# DEC8L-buscon.net
KiCad netlist of a schematic drawn in EAGLE
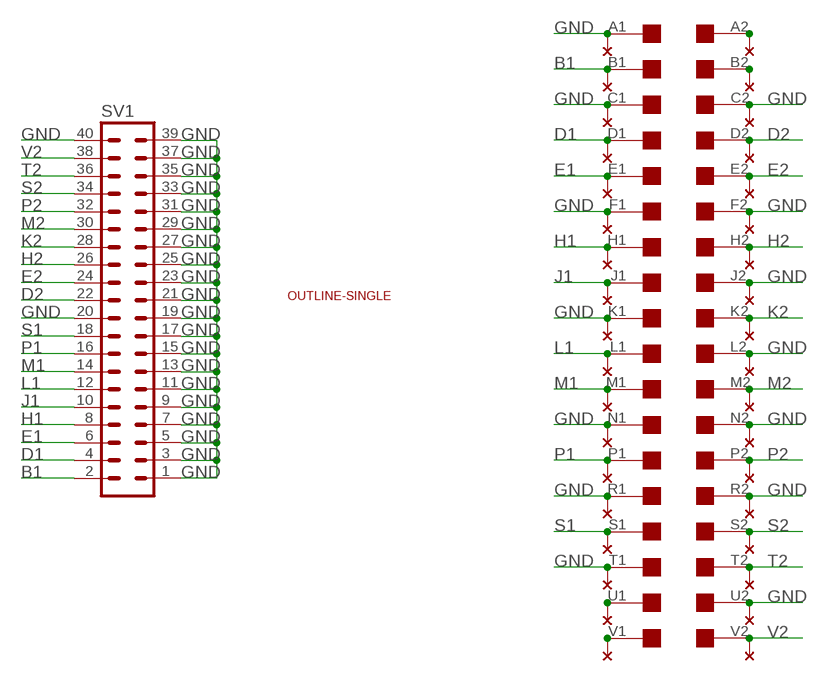
[diagram p0: schematic, sheet 1]

(export (version "E")
  (design (tool "Eeschema 10.0.6"))
  (components
    (comp (ref "EDGE1")
      (value "EDGE-2CONNECTOR")
      (footprint "eagle-import:EDGE-CON2")
      (libsource (lib "eagle-import") (part "EDGE-2CONNECTOR"))
    )
    (comp (ref "SV1")
      (value "MA20-2")
      (footprint "eagle-import:MA20-2")
      (libsource (lib "eagle-import") (part "MA20-2"))
    )
    (comp (ref "U$4")
      (value "OUTLINE-SINGLE")
      (footprint "eagle-import:SINGLE")
      (libsource (lib "eagle-import") (part "OUTLINE-SINGLE"))
    )
    (comp (ref "U$5")
      (value "THRU-HOLE2")
      (footprint "eagle-import:THRU-HOLEB")
      (libsource (lib "eagle-import") (part "THRU-HOLE2"))
    )
  )
  (nets
    (net (code "1") (name "/B1") (class "Default")
      (node (ref "EDGE1") (pin "B1") (pinfunction "1_B1") (pintype "bidirectional"))
      (node (ref "SV1") (pin "2") (pinfunction "2_2") (pintype "passive"))
      (node (ref "U$5") (pin "B1") (pinfunction "P$1_B1") (pintype "passive"))
    )
    (net (code "2") (name "/D1") (class "Default")
      (node (ref "EDGE1") (pin "D1") (pinfunction "1_D1") (pintype "bidirectional"))
      (node (ref "SV1") (pin "4") (pinfunction "4_4") (pintype "passive"))
      (node (ref "U$5") (pin "D1") (pinfunction "P$1_D1") (pintype "passive"))
    )
    (net (code "3") (name "/D2") (class "Default")
      (node (ref "EDGE1") (pin "D2") (pinfunction "1_D2") (pintype "bidirectional"))
      (node (ref "SV1") (pin "22") (pinfunction "22_22") (pintype "passive"))
      (node (ref "U$5") (pin "D2") (pinfunction "P$1_D2") (pintype "passive"))
    )
    (net (code "4") (name "/E1") (class "Default")
      (node (ref "EDGE1") (pin "E1") (pinfunction "1_E1") (pintype "bidirectional"))
      (node (ref "SV1") (pin "6") (pinfunction "6_6") (pintype "passive"))
      (node (ref "U$5") (pin "E1") (pinfunction "P$1_E1") (pintype "passive"))
    )
    (net (code "5") (name "/E2") (class "Default")
      (node (ref "EDGE1") (pin "E2") (pinfunction "1_E2") (pintype "bidirectional"))
      (node (ref "SV1") (pin "24") (pinfunction "24_24") (pintype "passive"))
      (node (ref "U$5") (pin "E2") (pinfunction "P$1_E2") (pintype "passive"))
    )
    (net (code "6") (name "/GND") (class "Default")
      (node (ref "EDGE1") (pin "A1") (pinfunction "1_A1") (pintype "bidirectional"))
      (node (ref "EDGE1") (pin "C1") (pinfunction "1_C1") (pintype "bidirectional"))
      (node (ref "EDGE1") (pin "C2") (pinfunction "1_C2") (pintype "bidirectional"))
      (node (ref "EDGE1") (pin "F1") (pinfunction "1_F1") (pintype "bidirectional"))
      (node (ref "EDGE1") (pin "F2") (pinfunction "1_F2") (pintype "bidirectional"))
      (node (ref "EDGE1") (pin "J2") (pinfunction "1_J2") (pintype "bidirectional"))
      (node (ref "EDGE1") (pin "K1") (pinfunction "1_K1") (pintype "bidirectional"))
      (node (ref "EDGE1") (pin "L2") (pinfunction "1_L2") (pintype "bidirectional"))
      (node (ref "EDGE1") (pin "N1") (pinfunction "1_N1") (pintype "bidirectional"))
      (node (ref "EDGE1") (pin "N2") (pinfunction "1_N2") (pintype "bidirectional"))
      (node (ref "EDGE1") (pin "R1") (pinfunction "1_R1") (pintype "bidirectional"))
      (node (ref "EDGE1") (pin "R2") (pinfunction "1_R2") (pintype "bidirectional"))
      (node (ref "EDGE1") (pin "T1") (pinfunction "1_T1") (pintype "bidirectional"))
      (node (ref "EDGE1") (pin "U2") (pinfunction "1_U2") (pintype "bidirectional"))
      (node (ref "SV1") (pin "1") (pinfunction "1_1") (pintype "passive"))
      (node (ref "SV1") (pin "11") (pinfunction "11_11") (pintype "passive"))
      (node (ref "SV1") (pin "13") (pinfunction "13_13") (pintype "passive"))
      (node (ref "SV1") (pin "15") (pinfunction "15_15") (pintype "passive"))
      (node (ref "SV1") (pin "17") (pinfunction "17_17") (pintype "passive"))
      (node (ref "SV1") (pin "19") (pinfunction "19_19") (pintype "passive"))
      (node (ref "SV1") (pin "20") (pinfunction "20_20") (pintype "passive"))
      (node (ref "SV1") (pin "21") (pinfunction "21_21") (pintype "passive"))
      (node (ref "SV1") (pin "23") (pinfunction "23_23") (pintype "passive"))
      (node (ref "SV1") (pin "25") (pinfunction "25_25") (pintype "passive"))
      (node (ref "SV1") (pin "27") (pinfunction "27_27") (pintype "passive"))
      (node (ref "SV1") (pin "29") (pinfunction "29_29") (pintype "passive"))
      (node (ref "SV1") (pin "3") (pinfunction "3_3") (pintype "passive"))
      (node (ref "SV1") (pin "31") (pinfunction "31_31") (pintype "passive"))
      (node (ref "SV1") (pin "33") (pinfunction "33_33") (pintype "passive"))
      (node (ref "SV1") (pin "35") (pinfunction "35_35") (pintype "passive"))
      (node (ref "SV1") (pin "37") (pinfunction "37_37") (pintype "passive"))
      (node (ref "SV1") (pin "39") (pinfunction "39_39") (pintype "passive"))
      (node (ref "SV1") (pin "40") (pinfunction "40_40") (pintype "passive"))
      (node (ref "SV1") (pin "5") (pinfunction "5_5") (pintype "passive"))
      (node (ref "SV1") (pin "7") (pinfunction "7_7") (pintype "passive"))
      (node (ref "SV1") (pin "9") (pinfunction "9_9") (pintype "passive"))
      (node (ref "U$5") (pin "A1") (pinfunction "P$1_A1") (pintype "passive"))
      (node (ref "U$5") (pin "C1") (pinfunction "P$1_C1") (pintype "passive"))
      (node (ref "U$5") (pin "C2") (pinfunction "P$1_C2") (pintype "passive"))
      (node (ref "U$5") (pin "F1") (pinfunction "P$1_F1") (pintype "passive"))
      (node (ref "U$5") (pin "F2") (pinfunction "P$1_F2") (pintype "passive"))
      (node (ref "U$5") (pin "J2") (pinfunction "P$1_J2") (pintype "passive"))
      (node (ref "U$5") (pin "K1") (pinfunction "P$1_K1") (pintype "passive"))
      (node (ref "U$5") (pin "L2") (pinfunction "P$1_L2") (pintype "passive"))
      (node (ref "U$5") (pin "N1") (pinfunction "P$1_N1") (pintype "passive"))
      (node (ref "U$5") (pin "N2") (pinfunction "P$1_N2") (pintype "passive"))
      (node (ref "U$5") (pin "R1") (pinfunction "P$1_R1") (pintype "passive"))
      (node (ref "U$5") (pin "R2") (pinfunction "P$1_R2") (pintype "passive"))
      (node (ref "U$5") (pin "T1") (pinfunction "P$1_T1") (pintype "passive"))
      (node (ref "U$5") (pin "U2") (pinfunction "P$1_U2") (pintype "passive"))
    )
    (net (code "7") (name "/H1") (class "Default")
      (node (ref "EDGE1") (pin "H1") (pinfunction "1_H1") (pintype "bidirectional"))
      (node (ref "SV1") (pin "8") (pinfunction "8_8") (pintype "passive"))
      (node (ref "U$5") (pin "H1") (pinfunction "P$1_H1") (pintype "passive"))
    )
    (net (code "8") (name "/H2") (class "Default")
      (node (ref "EDGE1") (pin "H2") (pinfunction "1_H2") (pintype "bidirectional"))
      (node (ref "SV1") (pin "26") (pinfunction "26_26") (pintype "passive"))
      (node (ref "U$5") (pin "H2") (pinfunction "P$1_H2") (pintype "passive"))
    )
    (net (code "9") (name "/J1") (class "Default")
      (node (ref "EDGE1") (pin "J1") (pinfunction "1_J1") (pintype "bidirectional"))
      (node (ref "SV1") (pin "10") (pinfunction "10_10") (pintype "passive"))
      (node (ref "U$5") (pin "J1") (pinfunction "P$1_J1") (pintype "passive"))
    )
    (net (code "10") (name "/K2") (class "Default")
      (node (ref "EDGE1") (pin "K2") (pinfunction "1_K2") (pintype "bidirectional"))
      (node (ref "SV1") (pin "28") (pinfunction "28_28") (pintype "passive"))
      (node (ref "U$5") (pin "K2") (pinfunction "P$1_K2") (pintype "passive"))
    )
    (net (code "11") (name "/L1") (class "Default")
      (node (ref "EDGE1") (pin "L1") (pinfunction "1_L1") (pintype "bidirectional"))
      (node (ref "SV1") (pin "12") (pinfunction "12_12") (pintype "passive"))
      (node (ref "U$5") (pin "L1") (pinfunction "P$1_L1") (pintype "passive"))
    )
    (net (code "12") (name "/M1") (class "Default")
      (node (ref "EDGE1") (pin "M1") (pinfunction "1_M1") (pintype "bidirectional"))
      (node (ref "SV1") (pin "14") (pinfunction "14_14") (pintype "passive"))
      (node (ref "U$5") (pin "M1") (pinfunction "P$1_M1") (pintype "passive"))
    )
    (net (code "13") (name "/M2") (class "Default")
      (node (ref "EDGE1") (pin "M2") (pinfunction "1_M2") (pintype "bidirectional"))
      (node (ref "SV1") (pin "30") (pinfunction "30_30") (pintype "passive"))
      (node (ref "U$5") (pin "M2") (pinfunction "P$1_M2") (pintype "passive"))
    )
    (net (code "14") (name "/P1") (class "Default")
      (node (ref "EDGE1") (pin "P1") (pinfunction "1_P1") (pintype "bidirectional"))
      (node (ref "SV1") (pin "16") (pinfunction "16_16") (pintype "passive"))
      (node (ref "U$5") (pin "P1") (pinfunction "P$1_P1") (pintype "passive"))
    )
    (net (code "15") (name "/P2") (class "Default")
      (node (ref "EDGE1") (pin "P2") (pinfunction "1_P2") (pintype "bidirectional"))
      (node (ref "SV1") (pin "32") (pinfunction "32_32") (pintype "passive"))
      (node (ref "U$5") (pin "P2") (pinfunction "P$1_P2") (pintype "passive"))
    )
    (net (code "16") (name "/S1") (class "Default")
      (node (ref "EDGE1") (pin "S1") (pinfunction "1_S1") (pintype "bidirectional"))
      (node (ref "SV1") (pin "18") (pinfunction "18_18") (pintype "passive"))
      (node (ref "U$5") (pin "S1") (pinfunction "P$1_S1") (pintype "passive"))
    )
    (net (code "17") (name "/S2") (class "Default")
      (node (ref "EDGE1") (pin "S2") (pinfunction "1_S2") (pintype "bidirectional"))
      (node (ref "SV1") (pin "34") (pinfunction "34_34") (pintype "passive"))
      (node (ref "U$5") (pin "S2") (pinfunction "P$1_S2") (pintype "passive"))
    )
    (net (code "18") (name "/T2") (class "Default")
      (node (ref "EDGE1") (pin "T2") (pinfunction "1_T2") (pintype "bidirectional"))
      (node (ref "SV1") (pin "36") (pinfunction "36_36") (pintype "passive"))
      (node (ref "U$5") (pin "T2") (pinfunction "P$1_T2") (pintype "passive"))
    )
    (net (code "19") (name "/V2") (class "Default")
      (node (ref "EDGE1") (pin "V2") (pinfunction "1_V2") (pintype "bidirectional"))
      (node (ref "SV1") (pin "38") (pinfunction "38_38") (pintype "passive"))
      (node (ref "U$5") (pin "V2") (pinfunction "P$1_V2") (pintype "passive"))
    )
    (net (code "20") (name "Net-(EDGE1AG-1)") (class "Default")
      (node (ref "EDGE1") (pin "U1") (pinfunction "1_U1") (pintype "bidirectional"))
      (node (ref "U$5") (pin "U1") (pinfunction "P$1_U1") (pintype "passive"))
    )
    (net (code "21") (name "Net-(EDGE1AI-1)") (class "Default")
      (node (ref "EDGE1") (pin "V1") (pinfunction "1_V1") (pintype "bidirectional"))
      (node (ref "U$5") (pin "V1") (pinfunction "P$1_V1") (pintype "passive"))
    )
    (net (code "22") (name "Net-(EDGE1B-1)") (class "Default")
      (node (ref "EDGE1") (pin "A2") (pinfunction "1_A2") (pintype "bidirectional"))
      (node (ref "U$5") (pin "A2") (pinfunction "P$1_A2") (pintype "passive"))
    )
    (net (code "23") (name "Net-(EDGE1D-1)") (class "Default")
      (node (ref "EDGE1") (pin "B2") (pinfunction "1_B2") (pintype "bidirectional"))
      (node (ref "U$5") (pin "B2") (pinfunction "P$1_B2") (pintype "passive"))
    )
  )
)
